# MCU.net
KiCad netlist of a schematic drawn in Altium Designer
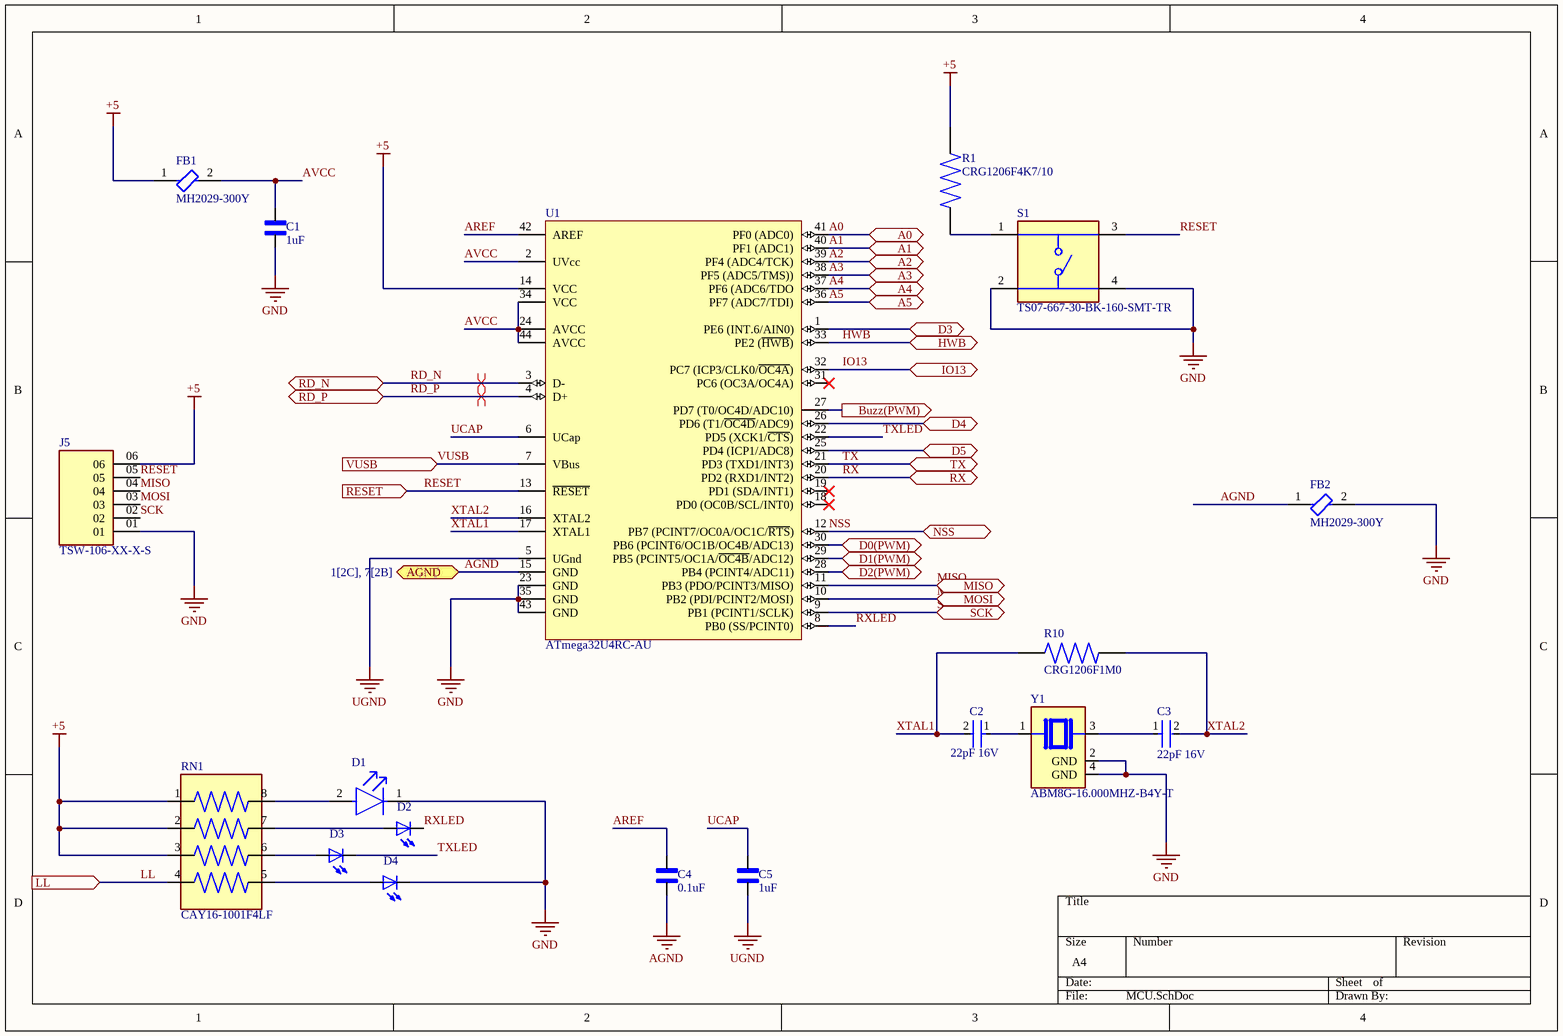
[diagram p0: MCU.SchDoc]

(export (version "E")
  (design (tool "Eeschema 10.0.6"))
  (components
    (comp (ref "C1")
      (value "1uF")
      (footprint "CAPC1608X90N")
      (fields (field (name "MP") "C0603C105K4RAC7411"))
      (libsource (lib "RFID") (part "C0603C105K4RAC7411"))
    )
    (comp (ref "C2")
      (value "22pF 16V")
      (footprint "FP-C0603C-CF-MFG")
      (description "CAP CER 22PF 50V X7R 0603\r\nC0603C220K5RACTU")
      (fields (field (name "MANUFACTURER PART NUMBER") "C0603C220K5RACTU") (field (name "TOLERANCE") "0.1"))
      (libsource (lib "Altium Content Vault") (part "b4654b650e69147ec39a6b967a45e02"))
    )
    (comp (ref "C3")
      (value "22pF 16V")
      (footprint "FP-C0603C-CF-MFG")
      (description "CAP CER 22PF 50V X7R 0603\r\nC0603C220K5RACTU")
      (fields (field (name "MANUFACTURER PART NUMBER") "C0603C220K5RACTU") (field (name "TOLERANCE") "0.1"))
      (libsource (lib "Altium Content Vault") (part "b4654b650e69147ec39a6b967a45e02"))
    )
    (comp (ref "C4")
      (value "0.1uF")
      (footprint "CAPC1608X90")
      (description "Capacitor;Ceramic;Cap;.0.1uF;Tol+5%;SMT;Vol-Rtg 16V;X7R;TR ¦ KEMET C0603C104J4RACTU")
      (fields (field (name "MF") "KEMET") (field (name "MP") "C0603C104J4RACTU"))
      (libsource (lib "RFID") (part "C0603C104J4RACTU"))
    )
    (comp (ref "C5")
      (value "1uF")
      (footprint "CAPC1608X90N")
      (fields (field (name "MP") "C0603C105K4RAC7411"))
      (libsource (lib "RFID") (part "C0603C105K4RAC7411"))
    )
    (comp (ref "D1")
      (value "LTST-C171KGKT")
      (footprint "FP-LTST-C171KGKT-MFG")
      (description "LED GREEN CLEAR SMD")
      (libsource (lib "Altium Content Vault") (part "8706943c75ba83719d021d2fdc84c58"))
    )
    (comp (ref "D2")
      (value "LTST-C171KSKT")
      (footprint "DIOC200X125X110")
      (description "Yellow 587nm LED Indication - Discrete 2V 0805 (2012 Metric)")
      (fields (field (name "MF") "Lite-On Inc."))
      (libsource (lib "Yellow_LED") (part "LTST-C171KSKT"))
    )
    (comp (ref "D3")
      (value "LTST-C171KSKT")
      (footprint "DIOC200X125X110")
      (description "Yellow 587nm LED Indication - Discrete 2V 0805 (2012 Metric)")
      (fields (field (name "MF") "Lite-On Inc."))
      (libsource (lib "Yellow_LED") (part "LTST-C171KSKT"))
    )
    (comp (ref "D4")
      (value "LTST-C171KSKT")
      (footprint "DIOC200X125X110")
      (description "Yellow 587nm LED Indication - Discrete 2V 0805 (2012 Metric)")
      (fields (field (name "MF") "Lite-On Inc."))
      (libsource (lib "Yellow_LED") (part "LTST-C171KSKT"))
    )
    (comp (ref "FB1")
      (value "MH2029-300Y")
      (footprint "FP-MH2029-IPC_A")
      (description "FERRITE BEAD 30 OHM 0805 1LN")
      (fields
        (field (name "OCTOPART") "https://octopart.com/mh2029-300y-bourns-756929")
        (field (name "MANUFACTURER") "Bourns")
      )
      (libsource (lib "RFID") (part "CMP-07252-000001-1"))
    )
    (comp (ref "FB2")
      (value "MH2029-300Y")
      (footprint "FP-MH2029-IPC_A")
      (description "FERRITE BEAD 30 OHM 0805 1LN")
      (fields
        (field (name "OCTOPART") "https://octopart.com/mh2029-300y-bourns-756929")
        (field (name "MANUFACTURER") "Bourns")
      )
      (libsource (lib "RFID") (part "CMP-07252-000001-1"))
    )
    (comp (ref "J5")
      (value "TSW-106-XX-X-S")
      (footprint "SAMTEC_TSW-106-XX-X-S")
      (description "Connector Header Through Hole 6 position 0.100 (2.54mm)")
      (fields (field (name "MF") "Samtec") (field (name "MP") "TSW-106-26-T-S"))
      (libsource (lib "RFID") (part "TSW-106-XX-X-S"))
    )
    (comp (ref "R1")
      (value "CRG1206F4K7/10")
      (footprint "RESC3115X65N")
      (description "Res Thick Film 1206 4.7K Ohm 1% 0.25W(1/4W) Â±100ppm/C Pad SMD T/R")
      (fields (field (name "MF") "TE Connectivity") (field (name "TOLERANCE") "1%"))
      (libsource (lib "RFID") (part "CRG1206F4K7/10"))
    )
    (comp (ref "R10")
      (value "CRG1206F1M0")
      (footprint "RESC3115X65N")
      (description "Resistor, Thick Film, Res 1 Ohms, Pwr-Rtg 0.25 W, Tol 1%, SMT, 1206 ¦ TE Connectivity CRG1206F1M0")
      (fields (field (name "MF") "TE Connectivity") (field (name "TOLERANCE") "1%"))
      (libsource (lib "RFID") (part "CRG1206F1M0"))
    )
    (comp (ref "RN1")
      (value "CAY16-1001F4LF")
      (footprint "RESCAF80P320X160X60-8N")
      (description "Resistor,Thick Film,Networks & Arrays,1K Ohm,1%,8 Pin ¦ Bourns CAY16-1001F4LF")
      (fields (field (name "MF") "Bourns"))
      (libsource (lib "RFID") (part "CAY16-1001F4LF"))
    )
    (comp (ref "S1")
      (value "TS07-667-30-BK-160-SMT-TR")
      (footprint "SW_TS07-667-30-BK-160-SMT-TR")
      (description "6 x 6.7 mm, 3 mm Actuator Height, 160 gf, Black, Surface Mount, SPST, Tactile Switch")
      (fields (field (name "MF") "Same Sky"))
      (libsource (lib "RFID") (part "TS07-667-30-BK-160-SMT-TR"))
    )
    (comp (ref "U1")
      (value "ATmega32U4RC-AU")
      (footprint "44ML_N")
      (libsource (lib "Altium Content Vault") (part "MC-8B-ATM16U4-SQ44"))
    )
    (comp (ref "Y1")
      (value "ABM8G-16.000MHZ-B4Y-T")
      (footprint "XTAL_ABM8G-16.000MHZ-B4Y-T")
      (description "16 MHz Â±30ppm Kristal 10pF 80 Ohm 4-SMD, KurÅŸunsuz")
      (fields (field (name "MF") "Abracon"))
      (libsource (lib "RFID") (part "ABM8G-16.000MHZ-B4Y-T"))
    )
  )
  (nets
    (net (code "1") (name "+5") (class "Default")
      (node (ref "FB1") (pin "1") (pinfunction "1_1") (pintype "passive"))
      (node (ref "J5") (pin "06") (pinfunction "06_06") (pintype "passive"))
      (node (ref "R1") (pin "2") (pinfunction "2_2") (pintype "passive"))
      (node (ref "RN1") (pin "1") (pinfunction "1_1") (pintype "passive"))
      (node (ref "RN1") (pin "2") (pinfunction "2_2") (pintype "passive"))
      (node (ref "RN1") (pin "3") (pinfunction "3_3") (pintype "passive"))
      (node (ref "U1") (pin "14") (pinfunction "VCC_14") (pintype "power_in"))
    )
    (net (code "2") (name "/A0") (class "Default")
      (node (ref "U1") (pin "41") (pinfunction "PF0_(ADC0)_41") (pintype "bidirectional"))
    )
    (net (code "3") (name "/A1") (class "Default")
      (node (ref "U1") (pin "40") (pinfunction "PF1_(ADC1)_40") (pintype "bidirectional"))
    )
    (net (code "4") (name "/A2") (class "Default")
      (node (ref "U1") (pin "39") (pinfunction "PF4_(ADC4/TCK)_39") (pintype "bidirectional"))
    )
    (net (code "5") (name "/A3") (class "Default")
      (node (ref "U1") (pin "38") (pinfunction "PF5_(ADC5/TMS))_38") (pintype "bidirectional"))
    )
    (net (code "6") (name "/A4") (class "Default")
      (node (ref "U1") (pin "37") (pinfunction "PF6_(ADC6/TDO_37") (pintype "bidirectional"))
    )
    (net (code "7") (name "/A5") (class "Default")
      (node (ref "U1") (pin "36") (pinfunction "PF7_(ADC7/TDI)_36") (pintype "bidirectional"))
    )
    (net (code "8") (name "/AREF") (class "Default")
      (node (ref "C4") (pin "1") (pinfunction "1_1") (pintype "passive"))
      (node (ref "U1") (pin "42") (pinfunction "AREF_42") (pintype "passive"))
    )
    (net (code "9") (name "/AVCC") (class "Default")
      (node (ref "C1") (pin "2") (pinfunction "2_2") (pintype "passive"))
      (node (ref "FB1") (pin "2") (pinfunction "2_2") (pintype "passive"))
      (node (ref "U1") (pin "2") (pinfunction "UVcc_2") (pintype "power_in"))
      (node (ref "U1") (pin "24") (pinfunction "AVCC_24") (pintype "power_in"))
      (node (ref "U1") (pin "34") (pinfunction "VCC_34") (pintype "power_in"))
      (node (ref "U1") (pin "44") (pinfunction "AVCC_44") (pintype "power_in"))
    )
    (net (code "10") (name "/Buzz(PWM)") (class "Default")
      (node (ref "U1") (pin "27") (pinfunction "PD7_(T0/OC4D/ADC10)_27") (pintype "passive"))
    )
    (net (code "11") (name "/D0(PWM)") (class "Default")
      (node (ref "U1") (pin "30") (pinfunction "PB6_(PCINT6/OC1B/OC4B/ADC13)_30") (pintype "bidirectional"))
    )
    (net (code "12") (name "/D1(PWM)") (class "Default")
      (node (ref "U1") (pin "29") (pinfunction "PB5_(PCINT5/OC1A/~{OC4B}/ADC12)_29") (pintype "bidirectional"))
    )
    (net (code "13") (name "/D2(PWM)") (class "Default")
      (node (ref "U1") (pin "28") (pinfunction "PB4_(PCINT4/ADC11)_28") (pintype "bidirectional"))
    )
    (net (code "14") (name "/D3") (class "Default")
      (node (ref "U1") (pin "1") (pinfunction "PE6_(INT.6/AIN0)_1") (pintype "bidirectional"))
    )
    (net (code "15") (name "/D4") (class "Default")
      (node (ref "U1") (pin "26") (pinfunction "PD6_(T1/~{OC4D}/ADC9)_26") (pintype "bidirectional"))
    )
    (net (code "16") (name "/D5") (class "Default")
      (node (ref "U1") (pin "25") (pinfunction "PD4_(ICP1/ADC8)_25") (pintype "bidirectional"))
    )
    (net (code "17") (name "/HWB") (class "Default")
      (node (ref "U1") (pin "33") (pinfunction "PE2_(~{HWB})_33") (pintype "bidirectional"))
    )
    (net (code "18") (name "/IO13") (class "Default")
      (node (ref "U1") (pin "32") (pinfunction "PC7_(ICP3/CLK0/~{OC4A})_32") (pintype "bidirectional"))
    )
    (net (code "19") (name "/LL") (class "Default")
      (node (ref "RN1") (pin "4") (pinfunction "4_4") (pintype "passive"))
    )
    (net (code "20") (name "/MISO") (class "Default")
      (node (ref "J5") (pin "04") (pinfunction "04_04") (pintype "passive"))
      (node (ref "U1") (pin "11") (pinfunction "PB3_(PDO/PCINT3/MISO)_11") (pintype "bidirectional"))
    )
    (net (code "21") (name "/MOSI") (class "Default")
      (node (ref "J5") (pin "03") (pinfunction "03_03") (pintype "passive"))
      (node (ref "U1") (pin "10") (pinfunction "PB2_(PDI/PCINT2/MOSI)_10") (pintype "bidirectional"))
    )
    (net (code "22") (name "/NSS") (class "Default")
      (node (ref "U1") (pin "12") (pinfunction "PB7_(PCINT7/OC0A/OC1C/~{RTS})_12") (pintype "bidirectional"))
    )
    (net (code "23") (name "/RD_N") (class "Default")
      (node (ref "U1") (pin "3") (pinfunction "D-_3") (pintype "bidirectional"))
    )
    (net (code "24") (name "/RD_P") (class "Default")
      (node (ref "U1") (pin "4") (pinfunction "D+_4") (pintype "bidirectional"))
    )
    (net (code "25") (name "/RESET") (class "Default")
      (node (ref "J5") (pin "05") (pinfunction "05_05") (pintype "passive"))
      (node (ref "S1") (pin "3") (pinfunction "3_3") (pintype "passive"))
      (node (ref "U1") (pin "13") (pinfunction "~{RESET}_13") (pintype "passive"))
    )
    (net (code "26") (name "/RX") (class "Default")
      (node (ref "U1") (pin "20") (pinfunction "PD2_(RXD1/INT2)_20") (pintype "bidirectional"))
    )
    (net (code "27") (name "/RXLED") (class "Default")
      (node (ref "D2") (pin "NEG") (pinfunction "NEG_NEG") (pintype "passive"))
      (node (ref "U1") (pin "8") (pinfunction "PB0_(SS/PCINT0)_8") (pintype "bidirectional"))
    )
    (net (code "28") (name "/SCK") (class "Default")
      (node (ref "J5") (pin "02") (pinfunction "02_02") (pintype "passive"))
      (node (ref "U1") (pin "9") (pinfunction "PB1_(PCINT1/SCLK)_9") (pintype "bidirectional"))
    )
    (net (code "29") (name "/TX") (class "Default")
      (node (ref "U1") (pin "21") (pinfunction "PD3_(TXD1/INT3)_21") (pintype "bidirectional"))
    )
    (net (code "30") (name "/TXLED") (class "Default")
      (node (ref "D3") (pin "NEG") (pinfunction "NEG_NEG") (pintype "passive"))
      (node (ref "U1") (pin "22") (pinfunction "PD5_(XCK1/~{CTS})_22") (pintype "bidirectional"))
    )
    (net (code "31") (name "/UCAP") (class "Default")
      (node (ref "C5") (pin "2") (pinfunction "2_2") (pintype "passive"))
      (node (ref "U1") (pin "6") (pinfunction "UCap_6") (pintype "passive"))
    )
    (net (code "32") (name "/VUSB") (class "Default")
      (node (ref "U1") (pin "7") (pinfunction "VBus_7") (pintype "passive"))
    )
    (net (code "33") (name "/XTAL1") (class "Default")
      (node (ref "C2") (pin "2") (pinfunction "2_2") (pintype "passive"))
      (node (ref "R10") (pin "1") (pinfunction "1_1") (pintype "passive"))
      (node (ref "U1") (pin "17") (pinfunction "XTAL1_17") (pintype "passive"))
    )
    (net (code "34") (name "/XTAL2") (class "Default")
      (node (ref "C3") (pin "2") (pinfunction "2_2") (pintype "passive"))
      (node (ref "R10") (pin "2") (pinfunction "2_2") (pintype "passive"))
      (node (ref "U1") (pin "16") (pinfunction "XTAL2_16") (pintype "passive"))
    )
    (net (code "35") (name "AGND") (class "Default")
      (node (ref "C4") (pin "2") (pinfunction "2_2") (pintype "passive"))
      (node (ref "FB2") (pin "1") (pinfunction "1_1") (pintype "passive"))
      (node (ref "U1") (pin "15") (pinfunction "GND_15") (pintype "passive"))
    )
    (net (code "36") (name "GND") (class "Default")
      (node (ref "C1") (pin "1") (pinfunction "1_1") (pintype "passive"))
      (node (ref "D1") (pin "1") (pinfunction "C_1") (pintype "passive"))
      (node (ref "D4") (pin "NEG") (pinfunction "NEG_NEG") (pintype "passive"))
      (node (ref "FB2") (pin "2") (pinfunction "2_2") (pintype "passive"))
      (node (ref "J5") (pin "01") (pinfunction "01_01") (pintype "passive"))
      (node (ref "S1") (pin "2") (pinfunction "2_2") (pintype "passive"))
      (node (ref "S1") (pin "4") (pinfunction "4_4") (pintype "passive"))
      (node (ref "U1") (pin "23") (pinfunction "GND_23") (pintype "power_in"))
      (node (ref "U1") (pin "35") (pinfunction "GND_35") (pintype "power_in"))
      (node (ref "U1") (pin "43") (pinfunction "GND_43") (pintype "power_in"))
      (node (ref "Y1") (pin "2") (pinfunction "GND_2") (pintype "power_in"))
      (node (ref "Y1") (pin "4") (pinfunction "GND_4") (pintype "power_in"))
    )
    (net (code "37") (name "Net-(C2-Pad1)") (class "Default")
      (node (ref "C2") (pin "1") (pinfunction "1_1") (pintype "passive"))
      (node (ref "Y1") (pin "1") (pinfunction "1_1") (pintype "passive"))
    )
    (net (code "38") (name "Net-(D1-A)") (class "Default")
      (node (ref "D1") (pin "2") (pinfunction "A_2") (pintype "passive"))
      (node (ref "RN1") (pin "8") (pinfunction "8_8") (pintype "passive"))
    )
    (net (code "39") (name "Net-(D2-PadPOS)") (class "Default")
      (node (ref "D2") (pin "POS") (pinfunction "POS_POS") (pintype "passive"))
      (node (ref "RN1") (pin "7") (pinfunction "7_7") (pintype "passive"))
    )
    (net (code "40") (name "Net-(D3-PadPOS)") (class "Default")
      (node (ref "D3") (pin "POS") (pinfunction "POS_POS") (pintype "passive"))
      (node (ref "RN1") (pin "6") (pinfunction "6_6") (pintype "passive"))
    )
    (net (code "41") (name "Net-(D4-PadPOS)") (class "Default")
      (node (ref "D4") (pin "POS") (pinfunction "POS_POS") (pintype "passive"))
      (node (ref "RN1") (pin "5") (pinfunction "5_5") (pintype "passive"))
    )
    (net (code "42") (name "Net-(R1-Pad1)") (class "Default")
      (node (ref "R1") (pin "1") (pinfunction "1_1") (pintype "passive"))
      (node (ref "S1") (pin "1") (pinfunction "1_1") (pintype "passive"))
    )
    (net (code "43") (name "Net-(Y1-2)") (class "Default")
      (node (ref "C3") (pin "1") (pinfunction "1_1") (pintype "passive"))
      (node (ref "Y1") (pin "3") (pinfunction "2_3") (pintype "passive"))
    )
    (net (code "44") (name "UGND") (class "Default")
      (node (ref "C5") (pin "1") (pinfunction "1_1") (pintype "passive"))
      (node (ref "U1") (pin "5") (pinfunction "UGnd_5") (pintype "power_in"))
    )
    (net (code "45") (name "unconnected-(U1-PC6_(OC3A{slash}OC4A)-Pad31)") (class "Default")
      (node (ref "U1") (pin "31") (pinfunction "PC6_(OC3A/OC4A)_31") (pintype "bidirectional+no_connect"))
    )
    (net (code "46") (name "unconnected-(U1-PD0_(OC0B{slash}SCL{slash}INT0)-Pad18)") (class "Default")
      (node (ref "U1") (pin "18") (pinfunction "PD0_(OC0B/SCL/INT0)_18") (pintype "bidirectional+no_connect"))
    )
    (net (code "47") (name "unconnected-(U1-PD1_(SDA{slash}INT1)-Pad19)") (class "Default")
      (node (ref "U1") (pin "19") (pinfunction "PD1_(SDA/INT1)_19") (pintype "bidirectional+no_connect"))
    )
  )
)
